# SWR_Tandem_Match.net
KiCad netlist of a schematic drawn in Altium Designer
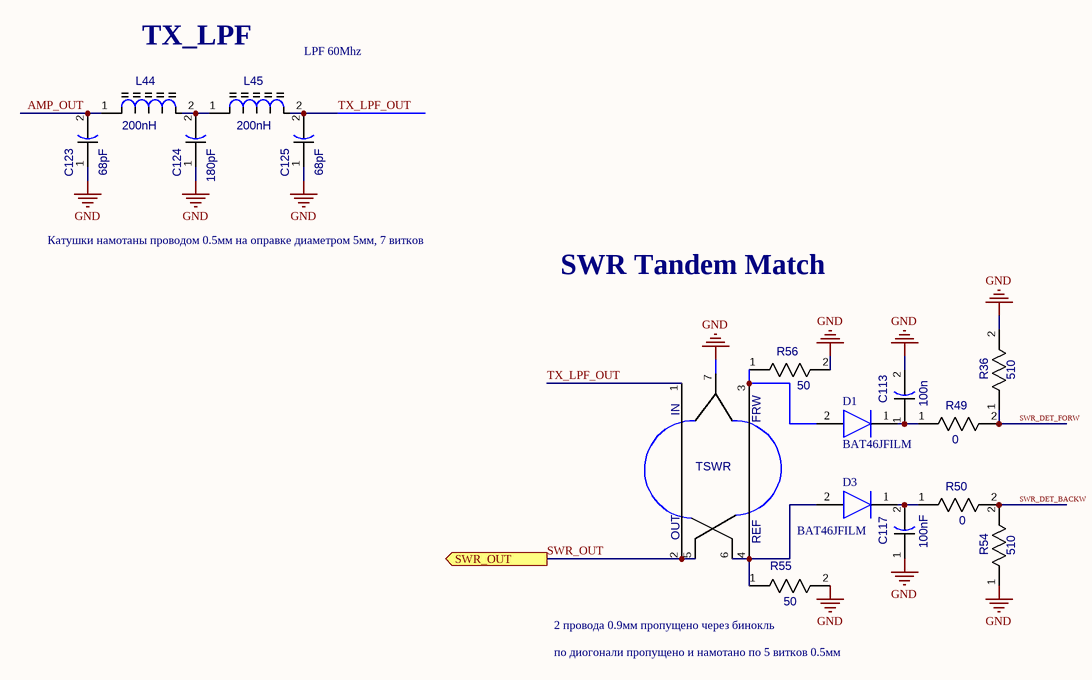
[diagram p0: SWR Tandem Match.SchDoc]

(export (version "E")
  (design (tool "Eeschema 10.0.6"))
  (components
    (comp (ref "C113")
      (value "100n")
      (footprint "CAP_0805")
      (description "CAP_0805")
      (libsource (lib "*") (part "CAP_0805"))
    )
    (comp (ref "C117")
      (value "100nF")
      (footprint "CAP_0805")
      (description "CAP_0805")
      (libsource (lib "*") (part "CAP_0805"))
    )
    (comp (ref "C123")
      (value "68pF")
      (footprint "CAP_1206")
      (description "CAP_1206")
      (libsource (lib "*") (part "CAP_1206"))
    )
    (comp (ref "C124")
      (value "180pF")
      (footprint "CAP_1206")
      (description "CAP_1206")
      (libsource (lib "*") (part "CAP_1206"))
    )
    (comp (ref "C125")
      (value "68pF")
      (footprint "CAP_1206")
      (description "CAP_1206")
      (libsource (lib "*") (part "CAP_1206"))
    )
    (comp (ref "D1")
      (value "BAT46JFILM")
      (footprint "SamacSys:SOD2513X117N")
      (description "Diode")
      (fields (field (name "MOUSER PART NUMBER") "511-BAT46JFILM") (field (name "RS PART NUMBER") "7146847P"))
      (libsource (lib "*") (part "BAT46JFILM"))
    )
    (comp (ref "D3")
      (value "BAT46JFILM")
      (footprint "SamacSys:SOD2513X117N")
      (description "Diode")
      (fields (field (name "MOUSER PART NUMBER") "511-BAT46JFILM") (field (name "RS PART NUMBER") "7146847P"))
      (libsource (lib "*") (part "BAT46JFILM"))
    )
    (comp (ref "L44")
      (value "200nH")
      (footprint "IND_FERRITE_CORE_1")
      (description "Inductor")
      (libsource (lib "*") (part "IND_FERRITE_CORE"))
    )
    (comp (ref "L45")
      (value "200nH")
      (footprint "IND_FERRITE_CORE_1")
      (description "Inductor")
      (libsource (lib "*") (part "IND_FERRITE_CORE"))
    )
    (comp (ref "R36")
      (value "510")
      (footprint "RES_0805")
      (description "RES_0805")
      (libsource (lib "*") (part "RES_0805"))
    )
    (comp (ref "R49")
      (value "0")
      (footprint "RES_0805")
      (description "RES_0805")
      (libsource (lib "*") (part "RES_0805"))
    )
    (comp (ref "R50")
      (value "0")
      (footprint "RES_0805")
      (description "RES_0805")
      (libsource (lib "*") (part "RES_0805"))
    )
    (comp (ref "R54")
      (value "510")
      (footprint "RES_0805")
      (description "RES_0805")
      (libsource (lib "*") (part "RES_0805"))
    )
    (comp (ref "R55")
      (value "50")
      (footprint "RES_1206")
      (description "RES_1206")
      (libsource (lib "*") (part "RES_1206"))
    )
    (comp (ref "R56")
      (value "50")
      (footprint "RES_1206")
      (description "RES_1206")
      (libsource (lib "*") (part "RES_1206"))
    )
    (comp (ref "TSWR")
      (value "SWR_TANDEM_MATCH")
      (footprint "SWR_TANDEM_MATCH")
      (libsource (lib "*") (part "SWR_TANDEM_MATCH"))
    )
  )
  (nets
    (net (code "1") (name "/AMP_OUT") (class "Default")
      (node (ref "C123") (pin "2") (pinfunction "2_2") (pintype "passive"))
      (node (ref "L44") (pin "1") (pinfunction "A_1") (pintype "passive"))
    )
    (net (code "2") (name "/SWR_DET_BACKW") (class "Default")
      (node (ref "R50") (pin "2") (pinfunction "2_2") (pintype "passive"))
      (node (ref "R54") (pin "2") (pinfunction "2_2") (pintype "passive"))
    )
    (net (code "3") (name "/SWR_DET_FORW") (class "Default")
      (node (ref "R36") (pin "1") (pinfunction "1_1") (pintype "passive"))
      (node (ref "R49") (pin "2") (pinfunction "2_2") (pintype "passive"))
    )
    (net (code "4") (name "/SWR_OUT") (class "Default")
      (node (ref "TSWR") (pin "2") (pinfunction "2_2") (pintype "passive"))
      (node (ref "TSWR") (pin "5") (pinfunction "5_5") (pintype "passive"))
    )
    (net (code "5") (name "/TX_LPF_OUT") (class "Default")
      (node (ref "C125") (pin "2") (pinfunction "2_2") (pintype "passive"))
      (node (ref "L45") (pin "2") (pinfunction "B_2") (pintype "passive"))
      (node (ref "TSWR") (pin "1") (pinfunction "1_1") (pintype "passive"))
    )
    (net (code "6") (name "GND") (class "Default")
      (node (ref "C113") (pin "2") (pinfunction "2_2") (pintype "passive"))
      (node (ref "C117") (pin "1") (pinfunction "1_1") (pintype "passive"))
      (node (ref "C123") (pin "1") (pinfunction "1_1") (pintype "passive"))
      (node (ref "C124") (pin "1") (pinfunction "1_1") (pintype "passive"))
      (node (ref "C125") (pin "1") (pinfunction "1_1") (pintype "passive"))
      (node (ref "R36") (pin "2") (pinfunction "2_2") (pintype "passive"))
      (node (ref "R54") (pin "1") (pinfunction "1_1") (pintype "passive"))
      (node (ref "R55") (pin "2") (pinfunction "2_2") (pintype "passive"))
      (node (ref "R56") (pin "2") (pinfunction "2_2") (pintype "passive"))
      (node (ref "TSWR") (pin "7") (pinfunction "7_7") (pintype "passive"))
    )
    (net (code "7") (name "Net-(D1-A)") (class "Default")
      (node (ref "D1") (pin "2") (pinfunction "A_2") (pintype "passive"))
      (node (ref "R56") (pin "1") (pinfunction "1_1") (pintype "passive"))
      (node (ref "TSWR") (pin "3") (pinfunction "3_3") (pintype "passive"))
    )
    (net (code "8") (name "Net-(D1-K)") (class "Default")
      (node (ref "C113") (pin "1") (pinfunction "1_1") (pintype "passive"))
      (node (ref "D1") (pin "1") (pinfunction "K_1") (pintype "passive"))
      (node (ref "R49") (pin "1") (pinfunction "1_1") (pintype "passive"))
    )
    (net (code "9") (name "Net-(D3-A)") (class "Default")
      (node (ref "D3") (pin "2") (pinfunction "A_2") (pintype "passive"))
      (node (ref "R55") (pin "1") (pinfunction "1_1") (pintype "passive"))
      (node (ref "TSWR") (pin "4") (pinfunction "4_4") (pintype "passive"))
      (node (ref "TSWR") (pin "6") (pinfunction "6_6") (pintype "passive"))
    )
    (net (code "10") (name "Net-(D3-K)") (class "Default")
      (node (ref "C117") (pin "2") (pinfunction "2_2") (pintype "passive"))
      (node (ref "D3") (pin "1") (pinfunction "K_1") (pintype "passive"))
      (node (ref "R50") (pin "1") (pinfunction "1_1") (pintype "passive"))
    )
    (net (code "11") (name "Net-(L44-B)") (class "Default")
      (node (ref "C124") (pin "2") (pinfunction "2_2") (pintype "passive"))
      (node (ref "L44") (pin "2") (pinfunction "B_2") (pintype "passive"))
      (node (ref "L45") (pin "1") (pinfunction "A_1") (pintype "passive"))
    )
  )
)
